# Oscar_MainBoard_MCU.net
KiCad netlist of a schematic drawn in Altium Designer
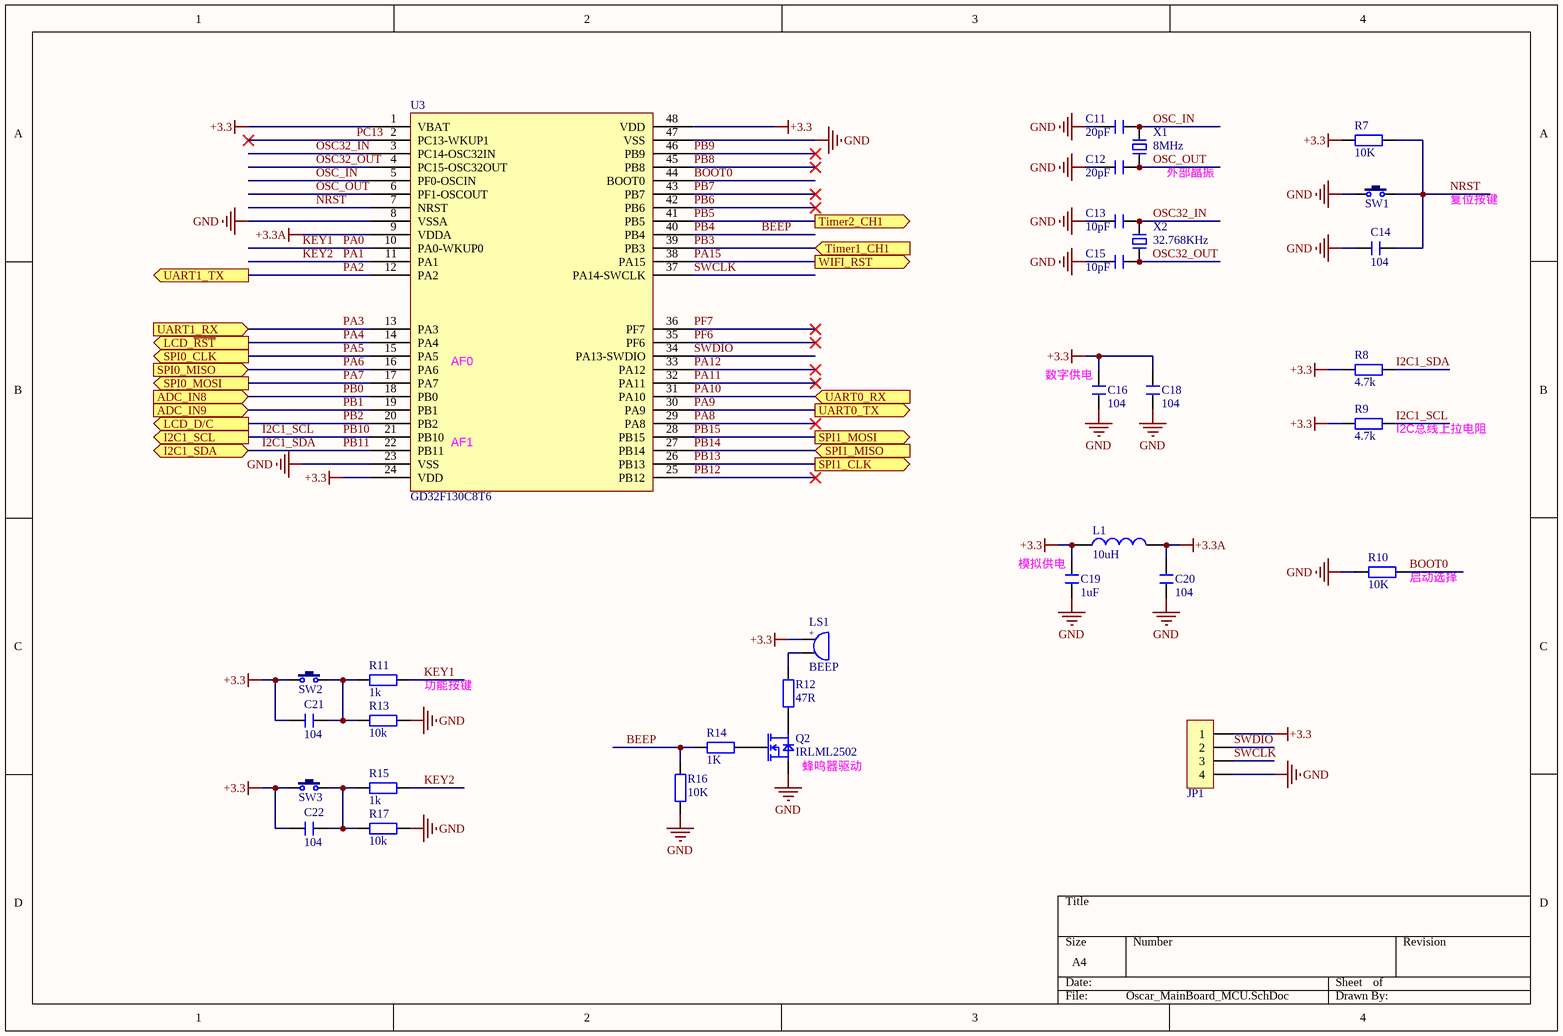
[diagram p0: Oscar_MainBoard_MCU.SchDoc]

(export (version "E")
  (design (tool "Eeschema 10.0.6"))
  (components
    (comp (ref "C11")
      (value "20pF")
      (footprint "C 0402_L")
      (description "贴片电容")
      (libsource (lib "0.1 - 电阻-电容-电感") (part "C"))
    )
    (comp (ref "C12")
      (value "20pF")
      (footprint "C 0402_L")
      (description "贴片电容")
      (libsource (lib "0.1 - 电阻-电容-电感") (part "C"))
    )
    (comp (ref "C13")
      (value "10pF")
      (footprint "C 0402_L")
      (description "贴片电容")
      (libsource (lib "0.1 - 电阻-电容-电感") (part "C"))
    )
    (comp (ref "C14")
      (value "104")
      (footprint "C 0402_L")
      (description "贴片电容")
      (libsource (lib "0.1 - 电阻-电容-电感") (part "C"))
    )
    (comp (ref "C15")
      (value "10pF")
      (footprint "C 0402_L")
      (description "贴片电容")
      (libsource (lib "0.1 - 电阻-电容-电感") (part "C"))
    )
    (comp (ref "C16")
      (value "104")
      (footprint "C 0402_L")
      (description "贴片电容")
      (libsource (lib "0.1 - 电阻-电容-电感") (part "C"))
    )
    (comp (ref "C18")
      (value "104")
      (footprint "C 0402_L")
      (description "贴片电容")
      (libsource (lib "0.1 - 电阻-电容-电感") (part "C"))
    )
    (comp (ref "C19")
      (value "1uF")
      (footprint "C 0402_L")
      (description "贴片电容")
      (libsource (lib "0.1 - 电阻-电容-电感") (part "C"))
    )
    (comp (ref "C20")
      (value "104")
      (footprint "C 0402_L")
      (description "贴片电容")
      (libsource (lib "0.1 - 电阻-电容-电感") (part "C"))
    )
    (comp (ref "C21")
      (value "104")
      (footprint "C 0402_L")
      (description "贴片电容")
      (libsource (lib "0.1 - 电阻-电容-电感") (part "C"))
    )
    (comp (ref "C22")
      (value "104")
      (footprint "C 0402_L")
      (description "贴片电容")
      (libsource (lib "0.1 - 电阻-电容-电感") (part "C"))
    )
    (comp (ref "JP1")
      (value "HDR-1X4")
      (footprint "HDR2.54-WS-4P")
      (description "4P接插件")
      (fields (field (name "版权归属") "封装库来自淘宝 ID：黄晶宝石"))
      (libsource (lib "5.4 - 接插件-脚距2.54 (100mil) ") (part "Header 4"))
    )
    (comp (ref "L1")
      (value "10uH")
      (footprint "L 0402")
      (description "小功率贴片电感")
      (libsource (lib "0.1 - 电阻-电容-电感") (part "L"))
    )
    (comp (ref "LS1")
      (value "BEEP")
      (footprint "BEEP 5020")
      (description "蜂鸣器")
      (libsource (lib "0.7 - 常用按键-开关-蜂鸣器-电池") (part "BEEP"))
    )
    (comp (ref "Q2")
      (value "IRLML2502")
      (footprint "SOT23-3n")
      (description "MOSFET N沟道 20V/4.2A")
      (libsource (lib "0.4 - 三极管-场效应管-可控硅") (part "IRLML2502"))
    )
    (comp (ref "R7")
      (value "10K")
      (footprint "R 0402_L")
      (description "贴片电阻")
      (libsource (lib "0.1 - 电阻-电容-电感") (part "R"))
    )
    (comp (ref "R8")
      (value "4.7k")
      (footprint "R 0402_L")
      (description "贴片电阻")
      (libsource (lib "0.1 - 电阻-电容-电感") (part "R"))
    )
    (comp (ref "R9")
      (value "4.7k")
      (footprint "R 0402_L")
      (description "贴片电阻")
      (libsource (lib "0.1 - 电阻-电容-电感") (part "R"))
    )
    (comp (ref "R10")
      (value "10K")
      (footprint "R 0402_L")
      (description "贴片电阻")
      (libsource (lib "0.1 - 电阻-电容-电感") (part "R"))
    )
    (comp (ref "R11")
      (value "1k")
      (footprint "R 0402_L")
      (description "贴片电阻")
      (libsource (lib "0.1 - 电阻-电容-电感") (part "R"))
    )
    (comp (ref "R12")
      (value "47R")
      (footprint "R 0402_L")
      (description "贴片电阻")
      (libsource (lib "0.1 - 电阻-电容-电感") (part "R"))
    )
    (comp (ref "R13")
      (value "10k")
      (footprint "R 0402_L")
      (description "贴片电阻")
      (libsource (lib "0.1 - 电阻-电容-电感") (part "R"))
    )
    (comp (ref "R14")
      (value "1K")
      (footprint "R 0402_L")
      (description "贴片电阻")
      (libsource (lib "0.1 - 电阻-电容-电感") (part "R"))
    )
    (comp (ref "R15")
      (value "1k")
      (footprint "R 0402_L")
      (description "贴片电阻")
      (libsource (lib "0.1 - 电阻-电容-电感") (part "R"))
    )
    (comp (ref "R16")
      (value "10K")
      (footprint "R 0402_L")
      (description "贴片电阻")
      (libsource (lib "0.1 - 电阻-电容-电感") (part "R"))
    )
    (comp (ref "R17")
      (value "10k")
      (footprint "R 0402_L")
      (description "贴片电阻")
      (libsource (lib "0.1 - 电阻-电容-电感") (part "R"))
    )
    (comp (ref "SW1")
      (value "TSW")
      (footprint "龟仔 3*4")
      (description "轻触开关")
      (fields (field (name "版权归属") "封装库来自淘宝 ID：黄晶宝石"))
      (libsource (lib "0.7 - 常用按键-开关-蜂鸣器-电池") (part "TSW"))
    )
    (comp (ref "SW2")
      (value "TSW")
      (footprint "龟仔 3*4")
      (description "轻触开关")
      (fields (field (name "版权归属") "封装库来自淘宝 ID：黄晶宝石"))
      (libsource (lib "0.7 - 常用按键-开关-蜂鸣器-电池") (part "TSW"))
    )
    (comp (ref "SW3")
      (value "TSW")
      (footprint "龟仔 3*4")
      (description "轻触开关")
      (fields (field (name "版权归属") "封装库来自淘宝 ID：黄晶宝石"))
      (libsource (lib "0.7 - 常用按键-开关-蜂鸣器-电池") (part "TSW"))
    )
    (comp (ref "U3")
      (value "GD32F130C8T6")
      (footprint "LQFP48_N")
      (description "64K 8K 48MHz")
      (libsource (lib "GD32") (part "GD32F130C8T6"))
    )
    (comp (ref "X1")
      (value "8MHz")
      (footprint "NDK 3225")
      (description "2脚无源脚晶振")
      (fields (field (name "版权归属") "封装库来自淘宝卖家 ID：黄晶宝石"))
      (libsource (lib "0.5 - 保险丝-晶振-光耦") (part "XTAL-2P"))
    )
    (comp (ref "X2")
      (value "32.768KHz")
      (footprint "FC-135")
      (description "2脚无源脚晶振")
      (fields (field (name "版权归属") "封装库来自淘宝卖家 ID：黄晶宝石"))
      (libsource (lib "0.5 - 保险丝-晶振-光耦") (part "XTAL-2P"))
    )
  )
  (nets
    (net (code "1") (name "+3.3") (class "Default")
      (node (ref "C16") (pin "2") (pinfunction "2_2") (pintype "passive"))
      (node (ref "C18") (pin "2") (pinfunction "2_2") (pintype "passive"))
      (node (ref "C19") (pin "2") (pinfunction "2_2") (pintype "passive"))
      (node (ref "C21") (pin "2") (pinfunction "2_2") (pintype "passive"))
      (node (ref "C22") (pin "2") (pinfunction "2_2") (pintype "passive"))
      (node (ref "JP1") (pin "1") (pinfunction "1_1") (pintype "passive"))
      (node (ref "L1") (pin "1") (pinfunction "1_1") (pintype "passive"))
      (node (ref "LS1") (pin "1") (pinfunction "1_1") (pintype "passive"))
      (node (ref "R7") (pin "2") (pinfunction "2_2") (pintype "passive"))
      (node (ref "R8") (pin "2") (pinfunction "2_2") (pintype "passive"))
      (node (ref "R9") (pin "2") (pinfunction "2_2") (pintype "passive"))
      (node (ref "SW2") (pin "1") (pinfunction "1_1") (pintype "passive"))
      (node (ref "SW3") (pin "1") (pinfunction "1_1") (pintype "passive"))
      (node (ref "U3") (pin "1") (pinfunction "VBAT_1") (pintype "passive"))
      (node (ref "U3") (pin "24") (pinfunction "VDD_24") (pintype "passive"))
      (node (ref "U3") (pin "48") (pinfunction "VDD_48") (pintype "passive"))
    )
    (net (code "2") (name "+3.3A") (class "Default")
      (node (ref "C20") (pin "2") (pinfunction "2_2") (pintype "passive"))
      (node (ref "L1") (pin "2") (pinfunction "2_2") (pintype "passive"))
      (node (ref "U3") (pin "9") (pinfunction "VDDA_9") (pintype "passive"))
    )
    (net (code "3") (name "/BEEP") (class "Default")
      (node (ref "R14") (pin "1") (pinfunction "1_1") (pintype "passive"))
      (node (ref "R16") (pin "2") (pinfunction "2_2") (pintype "passive"))
      (node (ref "U3") (pin "40") (pinfunction "PB4_40") (pintype "passive"))
    )
    (net (code "4") (name "/BOOT0") (class "Default")
      (node (ref "R10") (pin "2") (pinfunction "2_2") (pintype "passive"))
      (node (ref "U3") (pin "44") (pinfunction "BOOT0_44") (pintype "passive"))
    )
    (net (code "5") (name "/I2C1_SCL") (class "Default")
      (node (ref "R9") (pin "1") (pinfunction "1_1") (pintype "passive"))
      (node (ref "U3") (pin "21") (pinfunction "PB10_21") (pintype "passive"))
    )
    (net (code "6") (name "/I2C1_SDA") (class "Default")
      (node (ref "R8") (pin "1") (pinfunction "1_1") (pintype "passive"))
      (node (ref "U3") (pin "22") (pinfunction "PB11_22") (pintype "passive"))
    )
    (net (code "7") (name "/KEY1") (class "Default")
      (node (ref "R11") (pin "1") (pinfunction "1_1") (pintype "passive"))
      (node (ref "U3") (pin "10") (pinfunction "PA0-WKUP0_10") (pintype "passive"))
    )
    (net (code "8") (name "/KEY2") (class "Default")
      (node (ref "R15") (pin "1") (pinfunction "1_1") (pintype "passive"))
      (node (ref "U3") (pin "11") (pinfunction "PA1_11") (pintype "passive"))
    )
    (net (code "9") (name "/NRST") (class "Default")
      (node (ref "C14") (pin "2") (pinfunction "2_2") (pintype "passive"))
      (node (ref "R7") (pin "1") (pinfunction "1_1") (pintype "passive"))
      (node (ref "SW1") (pin "2") (pinfunction "2_2") (pintype "passive"))
      (node (ref "U3") (pin "7") (pinfunction "NRST_7") (pintype "passive"))
    )
    (net (code "10") (name "/OSC32_IN") (class "Default")
      (node (ref "C13") (pin "2") (pinfunction "2_2") (pintype "passive"))
      (node (ref "U3") (pin "3") (pinfunction "PC14-OSC32IN_3") (pintype "passive"))
      (node (ref "X2") (pin "2") (pinfunction "2_2") (pintype "passive"))
    )
    (net (code "11") (name "/OSC32_OUT") (class "Default")
      (node (ref "C15") (pin "2") (pinfunction "2_2") (pintype "passive"))
      (node (ref "U3") (pin "4") (pinfunction "PC15-OSC32OUT_4") (pintype "passive"))
      (node (ref "X2") (pin "1") (pinfunction "1_1") (pintype "passive"))
    )
    (net (code "12") (name "/OSC_IN") (class "Default")
      (node (ref "C11") (pin "2") (pinfunction "2_2") (pintype "passive"))
      (node (ref "U3") (pin "5") (pinfunction "PF0-OSCIN_5") (pintype "passive"))
      (node (ref "X1") (pin "2") (pinfunction "2_2") (pintype "passive"))
    )
    (net (code "13") (name "/OSC_OUT") (class "Default")
      (node (ref "C12") (pin "2") (pinfunction "2_2") (pintype "passive"))
      (node (ref "U3") (pin "6") (pinfunction "PF1-OSCOUT_6") (pintype "passive"))
      (node (ref "X1") (pin "1") (pinfunction "1_1") (pintype "passive"))
    )
    (net (code "14") (name "/PA2") (class "Default")
      (node (ref "U3") (pin "12") (pinfunction "PA2_12") (pintype "passive"))
    )
    (net (code "15") (name "/PA3") (class "Default")
      (node (ref "U3") (pin "13") (pinfunction "PA3_13") (pintype "passive"))
    )
    (net (code "16") (name "/PA4") (class "Default")
      (node (ref "U3") (pin "14") (pinfunction "PA4_14") (pintype "passive"))
    )
    (net (code "17") (name "/PA5") (class "Default")
      (node (ref "U3") (pin "15") (pinfunction "PA5_15") (pintype "passive"))
    )
    (net (code "18") (name "/PA6") (class "Default")
      (node (ref "U3") (pin "16") (pinfunction "PA6_16") (pintype "passive"))
    )
    (net (code "19") (name "/PA7") (class "Default")
      (node (ref "U3") (pin "17") (pinfunction "PA7_17") (pintype "passive"))
    )
    (net (code "20") (name "/PA8") (class "Default")
      (node (ref "U3") (pin "29") (pinfunction "PA8_29") (pintype "passive+no_connect"))
    )
    (net (code "21") (name "/PA9") (class "Default")
      (node (ref "U3") (pin "30") (pinfunction "PA9_30") (pintype "passive"))
    )
    (net (code "22") (name "/PA10") (class "Default")
      (node (ref "U3") (pin "31") (pinfunction "PA10_31") (pintype "passive"))
    )
    (net (code "23") (name "/PA11") (class "Default")
      (node (ref "U3") (pin "32") (pinfunction "PA11_32") (pintype "passive+no_connect"))
    )
    (net (code "24") (name "/PA12") (class "Default")
      (node (ref "U3") (pin "33") (pinfunction "PA12_33") (pintype "passive+no_connect"))
    )
    (net (code "25") (name "/PA15") (class "Default")
      (node (ref "U3") (pin "38") (pinfunction "PA15_38") (pintype "passive"))
    )
    (net (code "26") (name "/PB0") (class "Default")
      (node (ref "U3") (pin "18") (pinfunction "PB0_18") (pintype "passive"))
    )
    (net (code "27") (name "/PB1") (class "Default")
      (node (ref "U3") (pin "19") (pinfunction "PB1_19") (pintype "passive"))
    )
    (net (code "28") (name "/PB2") (class "Default")
      (node (ref "U3") (pin "20") (pinfunction "PB2_20") (pintype "passive"))
    )
    (net (code "29") (name "/PB3") (class "Default")
      (node (ref "U3") (pin "39") (pinfunction "PB3_39") (pintype "passive"))
    )
    (net (code "30") (name "/PB5") (class "Default")
      (node (ref "U3") (pin "41") (pinfunction "PB5_41") (pintype "passive"))
    )
    (net (code "31") (name "/PB6") (class "Default")
      (node (ref "U3") (pin "42") (pinfunction "PB6_42") (pintype "passive+no_connect"))
    )
    (net (code "32") (name "/PB7") (class "Default")
      (node (ref "U3") (pin "43") (pinfunction "PB7_43") (pintype "passive+no_connect"))
    )
    (net (code "33") (name "/PB8") (class "Default")
      (node (ref "U3") (pin "45") (pinfunction "PB8_45") (pintype "passive+no_connect"))
    )
    (net (code "34") (name "/PB9") (class "Default")
      (node (ref "U3") (pin "46") (pinfunction "PB9_46") (pintype "passive+no_connect"))
    )
    (net (code "35") (name "/PB12") (class "Default")
      (node (ref "U3") (pin "25") (pinfunction "PB12_25") (pintype "passive+no_connect"))
    )
    (net (code "36") (name "/PB13") (class "Default")
      (node (ref "U3") (pin "26") (pinfunction "PB13_26") (pintype "passive"))
    )
    (net (code "37") (name "/PB14") (class "Default")
      (node (ref "U3") (pin "27") (pinfunction "PB14_27") (pintype "passive"))
    )
    (net (code "38") (name "/PB15") (class "Default")
      (node (ref "U3") (pin "28") (pinfunction "PB15_28") (pintype "passive"))
    )
    (net (code "39") (name "/PC13") (class "Default")
      (node (ref "U3") (pin "2") (pinfunction "PC13-WKUP1_2") (pintype "passive+no_connect"))
    )
    (net (code "40") (name "/PF6") (class "Default")
      (node (ref "U3") (pin "35") (pinfunction "PF6_35") (pintype "passive+no_connect"))
    )
    (net (code "41") (name "/PF7") (class "Default")
      (node (ref "U3") (pin "36") (pinfunction "PF7_36") (pintype "passive+no_connect"))
    )
    (net (code "42") (name "/SWCLK") (class "Default")
      (node (ref "JP1") (pin "3") (pinfunction "3_3") (pintype "passive"))
      (node (ref "U3") (pin "37") (pinfunction "PA14-SWCLK_37") (pintype "passive"))
    )
    (net (code "43") (name "/SWDIO") (class "Default")
      (node (ref "JP1") (pin "2") (pinfunction "2_2") (pintype "passive"))
      (node (ref "U3") (pin "34") (pinfunction "PA13-SWDIO_34") (pintype "passive"))
    )
    (net (code "44") (name "GND") (class "Default")
      (node (ref "C11") (pin "1") (pinfunction "1_1") (pintype "passive"))
      (node (ref "C12") (pin "1") (pinfunction "1_1") (pintype "passive"))
      (node (ref "C13") (pin "1") (pinfunction "1_1") (pintype "passive"))
      (node (ref "C14") (pin "1") (pinfunction "1_1") (pintype "passive"))
      (node (ref "C15") (pin "1") (pinfunction "1_1") (pintype "passive"))
      (node (ref "C16") (pin "1") (pinfunction "1_1") (pintype "passive"))
      (node (ref "C18") (pin "1") (pinfunction "1_1") (pintype "passive"))
      (node (ref "C19") (pin "1") (pinfunction "1_1") (pintype "passive"))
      (node (ref "C20") (pin "1") (pinfunction "1_1") (pintype "passive"))
      (node (ref "JP1") (pin "4") (pinfunction "4_4") (pintype "passive"))
      (node (ref "Q2") (pin "2") (pinfunction "S_2") (pintype "passive"))
      (node (ref "R10") (pin "1") (pinfunction "1_1") (pintype "passive"))
      (node (ref "R13") (pin "1") (pinfunction "1_1") (pintype "passive"))
      (node (ref "R16") (pin "1") (pinfunction "1_1") (pintype "passive"))
      (node (ref "R17") (pin "1") (pinfunction "1_1") (pintype "passive"))
      (node (ref "SW1") (pin "1") (pinfunction "1_1") (pintype "passive"))
      (node (ref "U3") (pin "23") (pinfunction "VSS_23") (pintype "passive"))
      (node (ref "U3") (pin "47") (pinfunction "VSS_47") (pintype "passive"))
      (node (ref "U3") (pin "8") (pinfunction "VSSA_8") (pintype "passive"))
    )
    (net (code "45") (name "Net-(C21-Pad1)") (class "Default")
      (node (ref "C21") (pin "1") (pinfunction "1_1") (pintype "passive"))
      (node (ref "R11") (pin "2") (pinfunction "2_2") (pintype "passive"))
      (node (ref "R13") (pin "2") (pinfunction "2_2") (pintype "passive"))
      (node (ref "SW2") (pin "2") (pinfunction "2_2") (pintype "passive"))
    )
    (net (code "46") (name "Net-(C22-Pad1)") (class "Default")
      (node (ref "C22") (pin "1") (pinfunction "1_1") (pintype "passive"))
      (node (ref "R15") (pin "2") (pinfunction "2_2") (pintype "passive"))
      (node (ref "R17") (pin "2") (pinfunction "2_2") (pintype "passive"))
      (node (ref "SW3") (pin "2") (pinfunction "2_2") (pintype "passive"))
    )
    (net (code "47") (name "Net-(LS1-Pad2)") (class "Default")
      (node (ref "LS1") (pin "2") (pinfunction "2_2") (pintype "passive"))
      (node (ref "R12") (pin "2") (pinfunction "2_2") (pintype "passive"))
    )
    (net (code "48") (name "Net-(Q2-D)") (class "Default")
      (node (ref "Q2") (pin "3") (pinfunction "D_3") (pintype "passive"))
      (node (ref "R12") (pin "1") (pinfunction "1_1") (pintype "passive"))
    )
    (net (code "49") (name "Net-(Q2-G)") (class "Default")
      (node (ref "Q2") (pin "1") (pinfunction "G_1") (pintype "passive"))
      (node (ref "R14") (pin "2") (pinfunction "2_2") (pintype "passive"))
    )
  )
)
